# max5134.net
KiCad netlist of a schematic drawn in Altium Designer
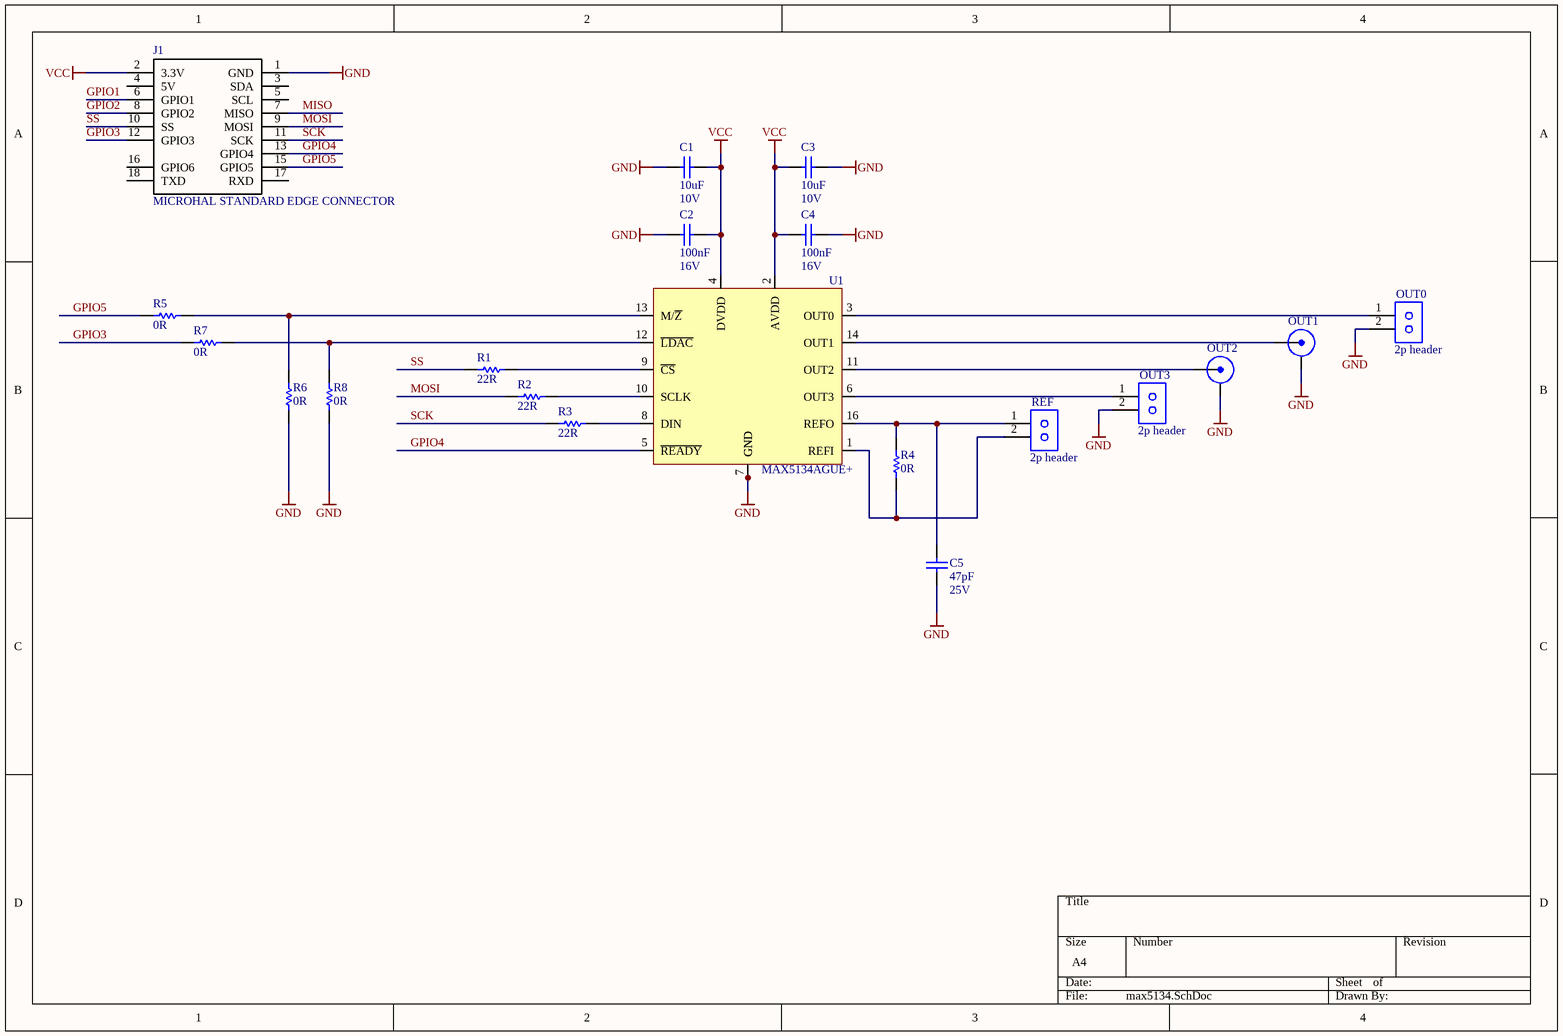
[diagram p0: max5134.SchDoc]

(export (version "E")
  (design (tool "Eeschema 10.0.6"))
  (components
    (comp (ref "C1")
      (value "10uF")
      (footprint "PCB-pgfgxap6j3hfn0qwxn05-1")
      (description "Cap Ceramic 10uF 10V X7R 10% Pad SMD 0805 Soft Termination 125C Automotive T/R")
      (fields (field (name "VOLTAGE") "10V") (field (name "Comment") "Cap"))
      (libsource (lib "CommunityVault") (part "CMP-0c34c7653e6ad3f3-1"))
    )
    (comp (ref "C2")
      (value "100nF")
      (footprint "PCB-ul7goghxin8pri3xfob7-1")
      (description "CL10 Series 0.1 uF 16 V ±10% Tolerance X7R SMT Multilayer Ceramic Capacitor")
      (fields (field (name "VOLTAGE") "16V") (field (name "Comment") "Cap"))
      (libsource (lib "CommunityVault") (part "CMP-4ca9852e0e1c936e-3"))
    )
    (comp (ref "C3")
      (value "10uF")
      (footprint "PCB-pgfgxap6j3hfn0qwxn05-1")
      (description "Cap Ceramic 10uF 10V X7R 10% Pad SMD 0805 Soft Termination 125C Automotive T/R")
      (fields (field (name "VOLTAGE") "10V") (field (name "Comment") "Cap"))
      (libsource (lib "CommunityVault") (part "CMP-0c34c7653e6ad3f3-1"))
    )
    (comp (ref "C4")
      (value "100nF")
      (footprint "PCB-ul7goghxin8pri3xfob7-1")
      (description "CL10 Series 0.1 uF 16 V ±10% Tolerance X7R SMT Multilayer Ceramic Capacitor")
      (fields (field (name "VOLTAGE") "16V") (field (name "Comment") "Cap"))
      (libsource (lib "CommunityVault") (part "CMP-4ca9852e0e1c936e-3"))
    )
    (comp (ref "C5")
      (value "Kemet C0603C470J3GACTU")
      (footprint "CAPC1608X87X35NL15T15")
      (description "Multilayer Ceramic Capacitors MLCC - SMD/SMT 25volts 47pF C0G 5%")
      (fields (field (name "CAPACITANCE") "47pF") (field (name "VOLTAGE RATING (DC)") "25V"))
      (libsource (lib "CommunityVault") (part "CMP-148602-2"))
    )
    (comp (ref "J1")
      (value "MICROHAL STANDARD EDGE CONNECTOR")
      (footprint "PCB-n61ghpg3sznbl2uw6fwj-1")
      (description "microhal standard edge connector with 17 pins")
      (libsource (lib "CommunityVault") (part "CMP-6a3uyflm72uf0am1b36s-2"))
    )
    (comp (ref "OUT0")
      (value "2p header")
      (footprint "PCB-b2cwpysm67pz35t2479s-1")
      (description "Board-To-Board Connector, Vertical, WR-PHD Series, Through Hole, Header, 2, 2.54 mm")
      (libsource (lib "CommunityVault") (part "SYM-748fbcb73d6bab48-4"))
    )
    (comp (ref "OUT1")
      (value "Amphenol Connex 132136RP")
      (footprint "PCB-qsvob2veabkktiupk4ti-1")
      (description "Connector; RF; SMA Right Angle PCB Jack Through Hole 50 Ohm Reverse Polarized")
      (fields (field (name "MANUFACTURER PART NUMBER") "132136RP"))
      (libsource (lib "CommunityVault") (part "CMP-acee67bfc04a7329-6"))
    )
    (comp (ref "OUT2")
      (value "Amphenol Connex 132136RP")
      (footprint "PCB-qsvob2veabkktiupk4ti-1")
      (description "Connector; RF; SMA Right Angle PCB Jack Through Hole 50 Ohm Reverse Polarized")
      (fields (field (name "MANUFACTURER PART NUMBER") "132136RP"))
      (libsource (lib "CommunityVault") (part "CMP-acee67bfc04a7329-6"))
    )
    (comp (ref "OUT3")
      (value "2p header")
      (footprint "PCB-b2cwpysm67pz35t2479s-1")
      (description "Board-To-Board Connector, Vertical, WR-PHD Series, Through Hole, Header, 2, 2.54 mm")
      (libsource (lib "CommunityVault") (part "SYM-748fbcb73d6bab48-4"))
    )
    (comp (ref "R1")
      (value "Vishay Dale CRCW060322R0JNEA")
      (footprint "RESC1609X50X30ML10T20")
      (description "RES SMD 22 OHM 5% 1/10W 0603")
      (fields (field (name "RESISTANCE") "22R"))
      (libsource (lib "CommunityVault") (part "CMP-1856016-2"))
    )
    (comp (ref "R2")
      (value "Vishay Dale CRCW060322R0JNEA")
      (footprint "RESC1609X50X30ML10T20")
      (description "RES SMD 22 OHM 5% 1/10W 0603")
      (fields (field (name "RESISTANCE") "22R"))
      (libsource (lib "CommunityVault") (part "CMP-1856016-2"))
    )
    (comp (ref "R3")
      (value "Vishay Dale CRCW060322R0JNEA")
      (footprint "RESC1609X50X30ML10T20")
      (description "RES SMD 22 OHM 5% 1/10W 0603")
      (fields (field (name "RESISTANCE") "22R"))
      (libsource (lib "CommunityVault") (part "CMP-1856016-2"))
    )
    (comp (ref "R4")
      (value "0R")
      (footprint "RESC1609X50X30ML10T20")
      (description "Resistor; Thick Film; 0 Ohms; 0.1 W; 0 Ohms Jumper; SMT; 0603; TCR 0 ppm/DegC; TR")
      (fields (field (name "Comment") "Res1"))
      (libsource (lib "CommunityVault") (part "CMP-1855984-13"))
    )
    (comp (ref "R5")
      (value "0R")
      (footprint "RESC1609X50X30ML10T20")
      (description "Resistor; Thick Film; 0 Ohms; 0.1 W; 0 Ohms Jumper; SMT; 0603; TCR 0 ppm/DegC; TR")
      (fields (field (name "Comment") "Res1"))
      (libsource (lib "CommunityVault") (part "CMP-1855984-13"))
    )
    (comp (ref "R6")
      (value "0R")
      (footprint "RESC1609X50X30ML10T20")
      (description "Resistor; Thick Film; 0 Ohms; 0.1 W; 0 Ohms Jumper; SMT; 0603; TCR 0 ppm/DegC; TR")
      (fields (field (name "Comment") "Res1"))
      (libsource (lib "CommunityVault") (part "CMP-1855984-13"))
    )
    (comp (ref "R7")
      (value "0R")
      (footprint "RESC1609X50X30ML10T20")
      (description "Resistor; Thick Film; 0 Ohms; 0.1 W; 0 Ohms Jumper; SMT; 0603; TCR 0 ppm/DegC; TR")
      (fields (field (name "Comment") "Res1"))
      (libsource (lib "CommunityVault") (part "CMP-1855984-13"))
    )
    (comp (ref "R8")
      (value "0R")
      (footprint "RESC1609X50X30ML10T20")
      (description "Resistor; Thick Film; 0 Ohms; 0.1 W; 0 Ohms Jumper; SMT; 0603; TCR 0 ppm/DegC; TR")
      (fields (field (name "Comment") "Res1"))
      (libsource (lib "CommunityVault") (part "CMP-1855984-13"))
    )
    (comp (ref "REF")
      (value "2p header")
      (footprint "PCB-b2cwpysm67pz35t2479s-1")
      (description "Board-To-Board Connector, Vertical, WR-PHD Series, Through Hole, Header, 2, 2.54 mm")
      (libsource (lib "CommunityVault") (part "SYM-748fbcb73d6bab48-4"))
    )
    (comp (ref "U1")
      (value "MAX5134AGUE+")
      (footprint "PCB-2k17843fb1qbvpte9n1l-1")
      (description "DAC 4-CH Resistor-String 16-bit 16-Pin TSSOP")
      (libsource (lib "CommunityVault") (part "CMP-b72d7cb8b58168ea-4"))
    )
  )
  (nets
    (net (code "1") (name "/GPIO1") (class "Default")
      (node (ref "J1") (pin "6") (pinfunction "GPIO1_6") (pintype "passive"))
    )
    (net (code "2") (name "/GPIO2") (class "Default")
      (node (ref "J1") (pin "8") (pinfunction "GPIO2_8") (pintype "passive"))
    )
    (net (code "3") (name "/GPIO3") (class "Default")
      (node (ref "J1") (pin "12") (pinfunction "GPIO3_12") (pintype "passive"))
      (node (ref "R7") (pin "2") (pinfunction "2_2") (pintype "passive"))
    )
    (net (code "4") (name "/GPIO4") (class "Default")
      (node (ref "J1") (pin "13") (pinfunction "GPIO4_13") (pintype "passive"))
      (node (ref "U1") (pin "5") (pinfunction "~{READY}_5") (pintype "passive"))
    )
    (net (code "5") (name "/GPIO5") (class "Default")
      (node (ref "J1") (pin "15") (pinfunction "GPIO5_15") (pintype "passive"))
      (node (ref "R5") (pin "2") (pinfunction "2_2") (pintype "passive"))
    )
    (net (code "6") (name "/MISO") (class "Default")
      (node (ref "J1") (pin "7") (pinfunction "MISO_7") (pintype "passive"))
    )
    (net (code "7") (name "/MOSI") (class "Default")
      (node (ref "J1") (pin "9") (pinfunction "MOSI_9") (pintype "passive"))
      (node (ref "R2") (pin "1") (pinfunction "1_1") (pintype "passive"))
    )
    (net (code "8") (name "/SCK") (class "Default")
      (node (ref "J1") (pin "11") (pinfunction "SCK_11") (pintype "passive"))
      (node (ref "R3") (pin "1") (pinfunction "1_1") (pintype "passive"))
    )
    (net (code "9") (name "/SS") (class "Default")
      (node (ref "J1") (pin "10") (pinfunction "SS_10") (pintype "passive"))
      (node (ref "R1") (pin "1") (pinfunction "1_1") (pintype "passive"))
    )
    (net (code "10") (name "GND") (class "Default")
      (node (ref "C1") (pin "2") (pinfunction "2_2") (pintype "passive"))
      (node (ref "C2") (pin "2") (pinfunction "2_2") (pintype "passive"))
      (node (ref "C3") (pin "1") (pinfunction "1_1") (pintype "passive"))
      (node (ref "C4") (pin "1") (pinfunction "1_1") (pintype "passive"))
      (node (ref "C5") (pin "2") (pinfunction "2_2") (pintype "passive"))
      (node (ref "J1") (pin "1") (pinfunction "GND_1") (pintype "passive"))
      (node (ref "OUT0") (pin "2") (pinfunction "2_2") (pintype "passive"))
      (node (ref "OUT1") (pin "2") (pinfunction "2_2") (pintype "passive"))
      (node (ref "OUT2") (pin "2") (pinfunction "2_2") (pintype "passive"))
      (node (ref "OUT3") (pin "2") (pinfunction "2_2") (pintype "passive"))
      (node (ref "R6") (pin "2") (pinfunction "2_2") (pintype "passive"))
      (node (ref "R8") (pin "2") (pinfunction "2_2") (pintype "passive"))
      (node (ref "U1") (pin "15") (pinfunction "GND_15") (pintype "passive"))
      (node (ref "U1") (pin "7") (pinfunction "GND_7") (pintype "passive"))
    )
    (net (code "11") (name "Net-(U1-DIN)") (class "Default")
      (node (ref "R3") (pin "2") (pinfunction "2_2") (pintype "passive"))
      (node (ref "U1") (pin "8") (pinfunction "DIN_8") (pintype "passive"))
    )
    (net (code "12") (name "Net-(U1-M{slash}~{Z})") (class "Default")
      (node (ref "R5") (pin "1") (pinfunction "1_1") (pintype "passive"))
      (node (ref "R6") (pin "1") (pinfunction "1_1") (pintype "passive"))
      (node (ref "U1") (pin "13") (pinfunction "M/~{Z}_13") (pintype "passive"))
    )
    (net (code "13") (name "Net-(U1-OUT0)") (class "Default")
      (node (ref "OUT0") (pin "1") (pinfunction "1_1") (pintype "passive"))
      (node (ref "U1") (pin "3") (pinfunction "OUT0_3") (pintype "passive"))
    )
    (net (code "14") (name "Net-(U1-OUT1)") (class "Default")
      (node (ref "OUT1") (pin "1") (pinfunction "1_1") (pintype "passive"))
      (node (ref "U1") (pin "14") (pinfunction "OUT1_14") (pintype "passive"))
    )
    (net (code "15") (name "Net-(U1-OUT2)") (class "Default")
      (node (ref "OUT2") (pin "1") (pinfunction "1_1") (pintype "passive"))
      (node (ref "U1") (pin "11") (pinfunction "OUT2_11") (pintype "passive"))
    )
    (net (code "16") (name "Net-(U1-OUT3)") (class "Default")
      (node (ref "OUT3") (pin "1") (pinfunction "1_1") (pintype "passive"))
      (node (ref "U1") (pin "6") (pinfunction "OUT3_6") (pintype "passive"))
    )
    (net (code "17") (name "Net-(U1-REFI)") (class "Default")
      (node (ref "R4") (pin "1") (pinfunction "1_1") (pintype "passive"))
      (node (ref "REF") (pin "2") (pinfunction "2_2") (pintype "passive"))
      (node (ref "U1") (pin "1") (pinfunction "REFI_1") (pintype "passive"))
    )
    (net (code "18") (name "Net-(U1-REFO)") (class "Default")
      (node (ref "C5") (pin "1") (pinfunction "1_1") (pintype "passive"))
      (node (ref "R4") (pin "2") (pinfunction "2_2") (pintype "passive"))
      (node (ref "REF") (pin "1") (pinfunction "1_1") (pintype "passive"))
      (node (ref "U1") (pin "16") (pinfunction "REFO_16") (pintype "passive"))
    )
    (net (code "19") (name "Net-(U1-SCLK)") (class "Default")
      (node (ref "R2") (pin "2") (pinfunction "2_2") (pintype "passive"))
      (node (ref "U1") (pin "10") (pinfunction "SCLK_10") (pintype "passive"))
    )
    (net (code "20") (name "Net-(U1-~{CS})") (class "Default")
      (node (ref "R1") (pin "2") (pinfunction "2_2") (pintype "passive"))
      (node (ref "U1") (pin "9") (pinfunction "~{CS}_9") (pintype "passive"))
    )
    (net (code "21") (name "Net-(U1-~{LDAC})") (class "Default")
      (node (ref "R7") (pin "1") (pinfunction "1_1") (pintype "passive"))
      (node (ref "R8") (pin "1") (pinfunction "1_1") (pintype "passive"))
      (node (ref "U1") (pin "12") (pinfunction "~{LDAC}_12") (pintype "passive"))
    )
    (net (code "22") (name "VCC") (class "Default")
      (node (ref "C1") (pin "1") (pinfunction "1_1") (pintype "passive"))
      (node (ref "C2") (pin "1") (pinfunction "1_1") (pintype "passive"))
      (node (ref "C3") (pin "2") (pinfunction "2_2") (pintype "passive"))
      (node (ref "C4") (pin "2") (pinfunction "2_2") (pintype "passive"))
      (node (ref "J1") (pin "2") (pinfunction "3.3V_2") (pintype "passive"))
      (node (ref "U1") (pin "2") (pinfunction "AVDD_2") (pintype "passive"))
      (node (ref "U1") (pin "4") (pinfunction "DVDD_4") (pintype "passive"))
    )
    (net (code "23") (name "unconnected-(J1-5V-Pad4)") (class "Default")
      (node (ref "J1") (pin "4") (pinfunction "5V_4") (pintype "passive"))
    )
    (net (code "24") (name "unconnected-(J1-GPIO6-Pad16)") (class "Default")
      (node (ref "J1") (pin "16") (pinfunction "GPIO6_16") (pintype "passive"))
    )
    (net (code "25") (name "unconnected-(J1-RXD-Pad17)") (class "Default")
      (node (ref "J1") (pin "17") (pinfunction "RXD_17") (pintype "passive"))
    )
    (net (code "26") (name "unconnected-(J1-SCL-Pad5)") (class "Default")
      (node (ref "J1") (pin "5") (pinfunction "SCL_5") (pintype "passive"))
    )
    (net (code "27") (name "unconnected-(J1-SDA-Pad3)") (class "Default")
      (node (ref "J1") (pin "3") (pinfunction "SDA_3") (pintype "passive"))
    )
    (net (code "28") (name "unconnected-(J1-TXD-Pad18)") (class "Default")
      (node (ref "J1") (pin "18") (pinfunction "TXD_18") (pintype "passive"))
    )
  )
)
